# hbridge1.net
KiCad netlist of a schematic drawn in EAGLE
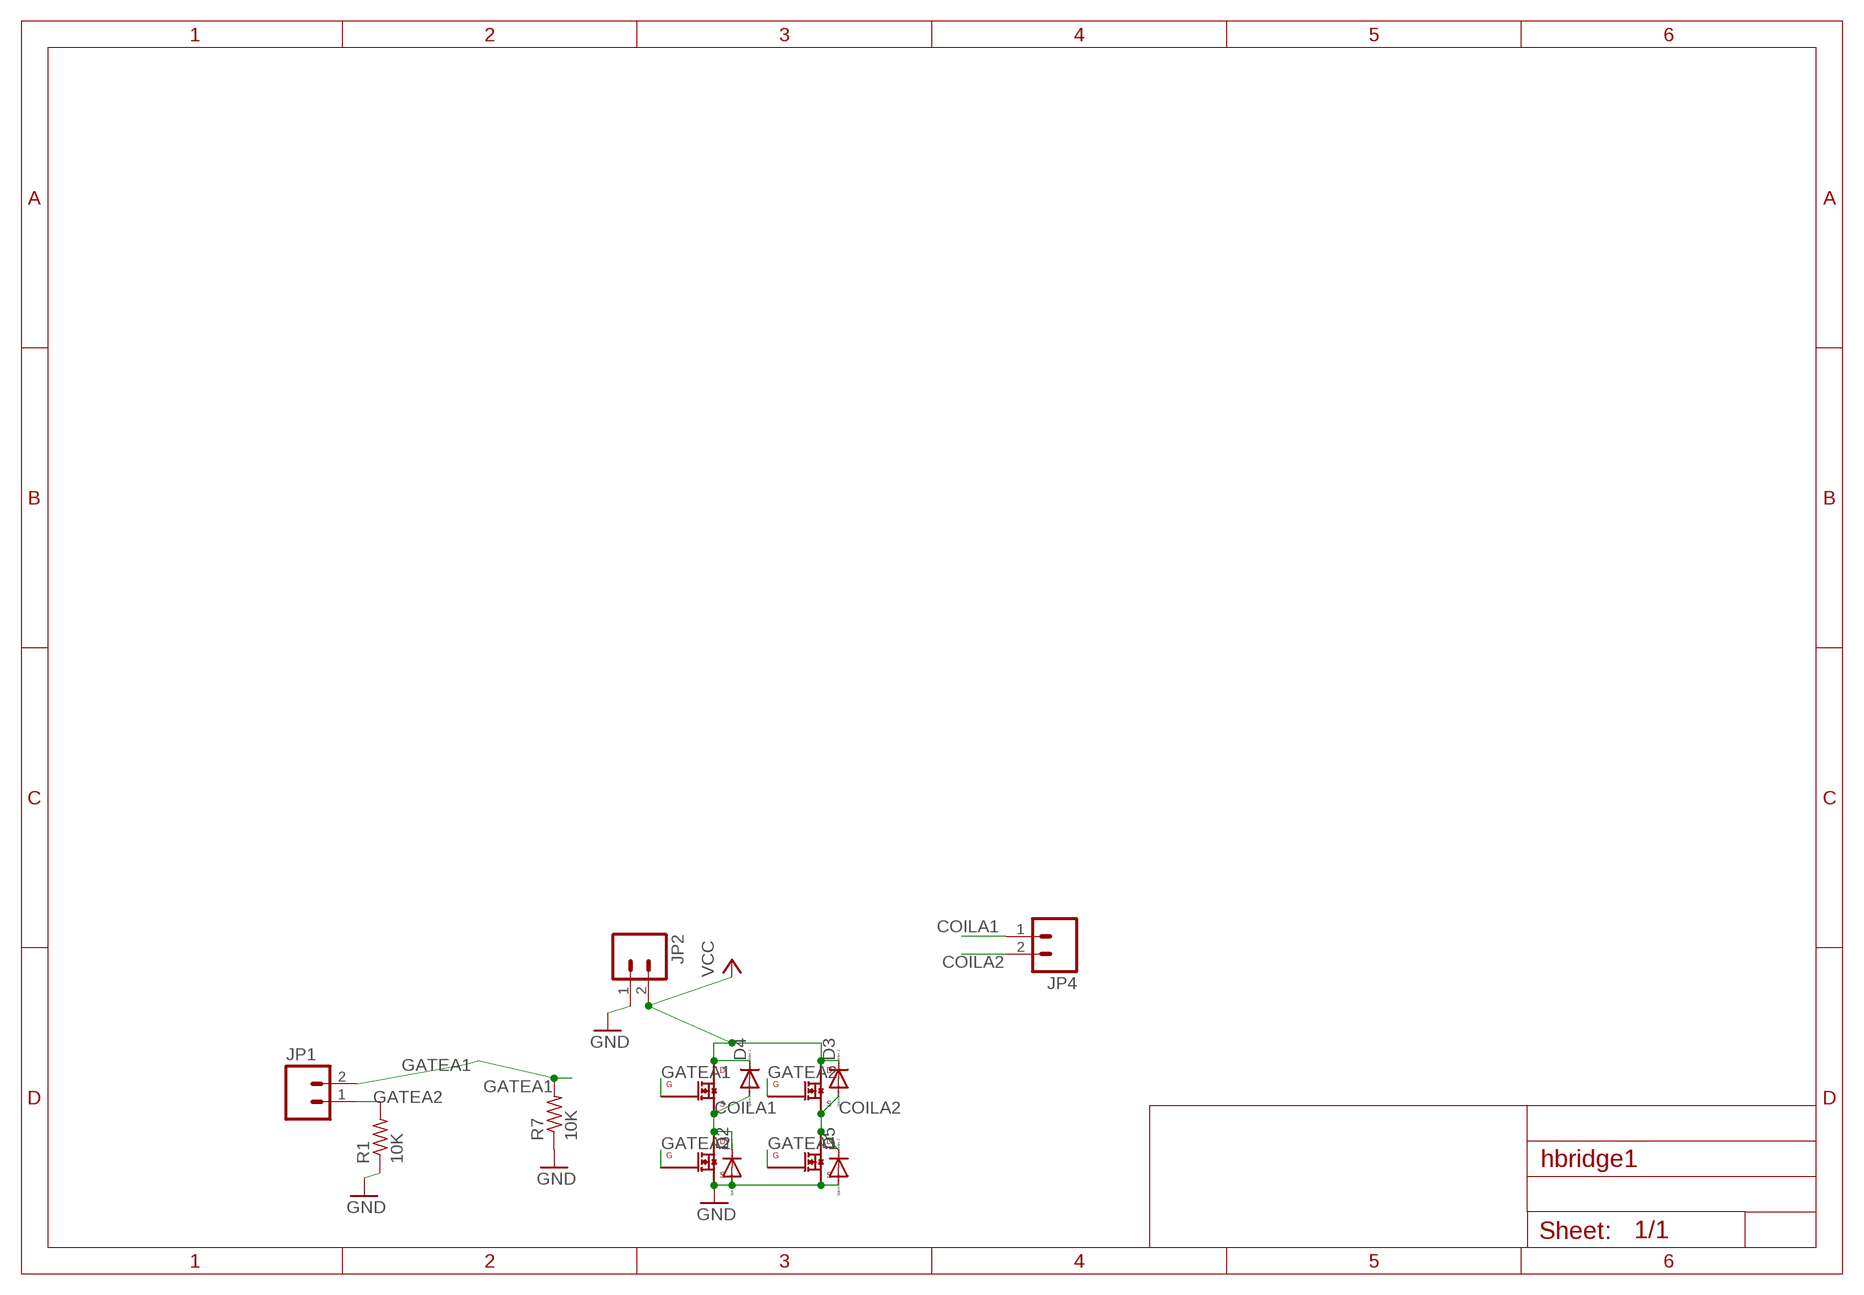
[diagram p0: schematic, sheet 1]

(export (version "E")
  (design (tool "Eeschema 10.0.6"))
  (components
    (comp (ref "D2")
      (value "DIODE-DO-214AC")
      (footprint "eagle-import:DO-214AC")
      (libsource (lib "eagle-import") (part "DIODE-DO-214AC"))
    )
    (comp (ref "D3")
      (value "DIODE-DO-214AC")
      (footprint "eagle-import:DO-214AC")
      (libsource (lib "eagle-import") (part "DIODE-DO-214AC"))
    )
    (comp (ref "D4")
      (value "DIODE-DO-214AC")
      (footprint "eagle-import:DO-214AC")
      (libsource (lib "eagle-import") (part "DIODE-DO-214AC"))
    )
    (comp (ref "D5")
      (value "DIODE-DO-214AC")
      (footprint "eagle-import:DO-214AC")
      (libsource (lib "eagle-import") (part "DIODE-DO-214AC"))
    )
    (comp (ref "JP1")
      (value "M02PTH")
      (footprint "eagle-import:1X02")
      (libsource (lib "eagle-import") (part "M02PTH"))
    )
    (comp (ref "JP2")
      (value "M02PTH")
      (footprint "eagle-import:1X02")
      (libsource (lib "eagle-import") (part "M02PTH"))
    )
    (comp (ref "JP4")
      (value "M02PTH")
      (footprint "eagle-import:1X02")
      (libsource (lib "eagle-import") (part "M02PTH"))
    )
    (comp (ref "Q2")
      (value "IRLML0060")
      (footprint "eagle-import:SOT-23")
      (libsource (lib "eagle-import") (part "IRLML0060"))
    )
    (comp (ref "Q3")
      (value "IRLML0060")
      (footprint "eagle-import:SOT-23")
      (libsource (lib "eagle-import") (part "IRLML0060"))
    )
    (comp (ref "Q4")
      (value "IRLML0060")
      (footprint "eagle-import:SOT-23")
      (libsource (lib "eagle-import") (part "IRLML0060"))
    )
    (comp (ref "Q5")
      (value "IRLML0060")
      (footprint "eagle-import:SOT-23")
      (libsource (lib "eagle-import") (part "IRLML0060"))
    )
    (comp (ref "R1")
      (value "10K")
      (footprint "eagle-import:R0603")
      (libsource (lib "eagle-import") (part "R-US_R0603"))
    )
    (comp (ref "R7")
      (value "10K")
      (footprint "eagle-import:R0603")
      (libsource (lib "eagle-import") (part "R-US_R0603"))
    )
  )
  (nets
    (net (code "1") (name "/COILA1") (class "Default")
      (node (ref "D2") (pin "C") (pinfunction "C_C") (pintype "passive"))
      (node (ref "D4") (pin "A") (pinfunction "A_A") (pintype "passive"))
      (node (ref "JP4") (pin "1") (pinfunction "1_1") (pintype "passive"))
      (node (ref "Q2") (pin "3") (pinfunction "DRAIN_3") (pintype "bidirectional"))
      (node (ref "Q4") (pin "2") (pinfunction "SOURCE_2") (pintype "bidirectional"))
    )
    (net (code "2") (name "/COILA2") (class "Default")
      (node (ref "D3") (pin "A") (pinfunction "A_A") (pintype "passive"))
      (node (ref "D5") (pin "C") (pinfunction "C_C") (pintype "passive"))
      (node (ref "JP4") (pin "2") (pinfunction "2_2") (pintype "passive"))
      (node (ref "Q3") (pin "2") (pinfunction "SOURCE_2") (pintype "bidirectional"))
      (node (ref "Q5") (pin "3") (pinfunction "DRAIN_3") (pintype "bidirectional"))
    )
    (net (code "3") (name "/GATEA1") (class "Default")
      (node (ref "JP1") (pin "2") (pinfunction "2_2") (pintype "passive"))
      (node (ref "Q4") (pin "1") (pinfunction "GATE_1") (pintype "bidirectional"))
      (node (ref "Q5") (pin "1") (pinfunction "GATE_1") (pintype "bidirectional"))
      (node (ref "R7") (pin "2") (pinfunction "2_2") (pintype "passive"))
    )
    (net (code "4") (name "/GATEA2") (class "Default")
      (node (ref "JP1") (pin "1") (pinfunction "1_1") (pintype "passive"))
      (node (ref "Q2") (pin "1") (pinfunction "GATE_1") (pintype "bidirectional"))
      (node (ref "Q3") (pin "1") (pinfunction "GATE_1") (pintype "bidirectional"))
      (node (ref "R1") (pin "2") (pinfunction "2_2") (pintype "passive"))
    )
    (net (code "5") (name "GND") (class "Default")
      (node (ref "D2") (pin "A") (pinfunction "A_A") (pintype "passive"))
      (node (ref "D5") (pin "A") (pinfunction "A_A") (pintype "passive"))
      (node (ref "JP2") (pin "1") (pinfunction "1_1") (pintype "passive"))
      (node (ref "Q2") (pin "2") (pinfunction "SOURCE_2") (pintype "bidirectional"))
      (node (ref "Q5") (pin "2") (pinfunction "SOURCE_2") (pintype "bidirectional"))
      (node (ref "R1") (pin "1") (pinfunction "1_1") (pintype "passive"))
      (node (ref "R7") (pin "1") (pinfunction "1_1") (pintype "passive"))
    )
    (net (code "6") (name "VCC") (class "Default")
      (node (ref "D3") (pin "C") (pinfunction "C_C") (pintype "passive"))
      (node (ref "D4") (pin "C") (pinfunction "C_C") (pintype "passive"))
      (node (ref "JP2") (pin "2") (pinfunction "2_2") (pintype "passive"))
      (node (ref "Q3") (pin "3") (pinfunction "DRAIN_3") (pintype "bidirectional"))
      (node (ref "Q4") (pin "3") (pinfunction "DRAIN_3") (pintype "bidirectional"))
    )
  )
)
